# DIP2350_RC0.net
KiCad netlist of a schematic drawn in Altium Designer
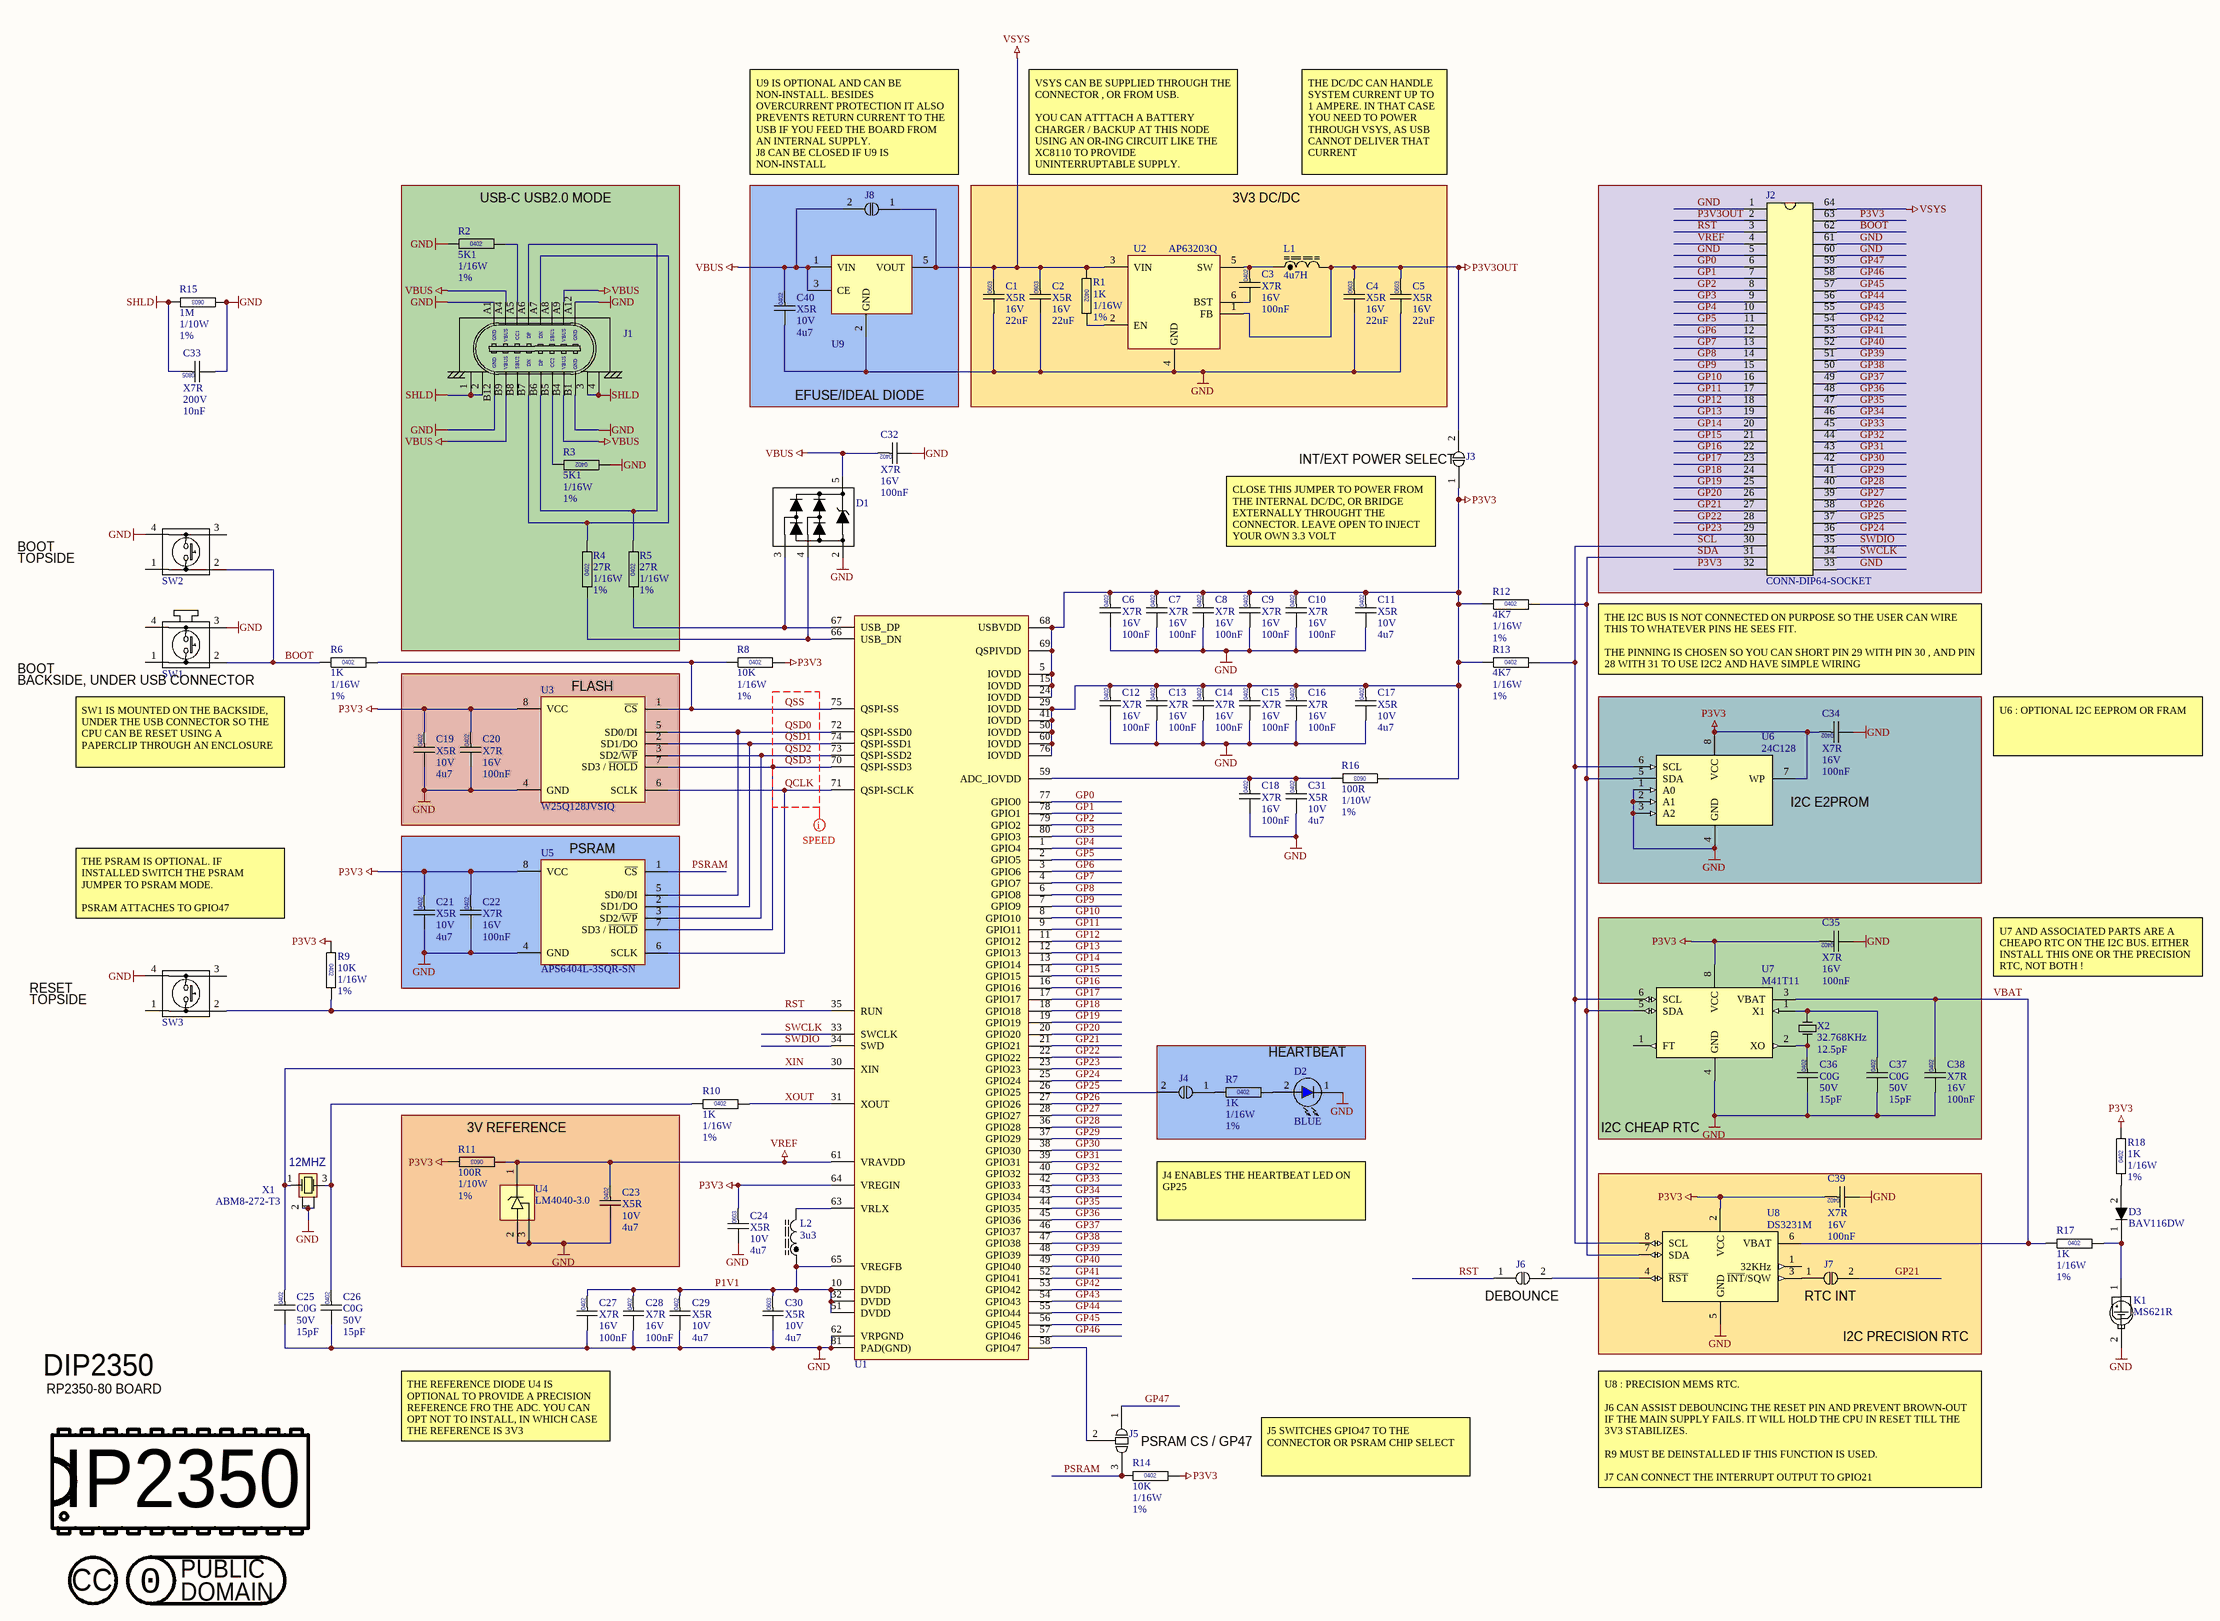
[diagram p0: DIP2350 RC0.SchDoc]

(export (version "E")
  (design (tool "Eeschema 10.0.6"))
  (components
    (comp (ref "C1")
      (value "CAP0603")
      (footprint "CAPC0603")
      (description "CAPACITOR,CERAMIC,22uF,16V,X5R,0603")
      (fields
        (field (name "DIELECTRIC") "X5R")
        (field (name "VOLTAGE") "16V")
        (field (name "CAPACITANCE") "22uF")
      )
      (libsource (lib "CAPACITORS") (part "CAPC-0603-22uF-16V-X5R"))
    )
    (comp (ref "C2")
      (value "CAP0603")
      (footprint "CAPC0603")
      (description "CAPACITOR,CERAMIC,22uF,16V,X5R,0603")
      (fields
        (field (name "DIELECTRIC") "X5R")
        (field (name "VOLTAGE") "16V")
        (field (name "CAPACITANCE") "22uF")
      )
      (libsource (lib "CAPACITORS") (part "CAPC-0603-22uF-16V-X5R"))
    )
    (comp (ref "C3")
      (value "CAP0402")
      (footprint "CAPC0402")
      (description "CAPACITOR,CERAMIC,100nF,16V,X7R,0402")
      (fields
        (field (name "DIELECTRIC") "X7R")
        (field (name "VOLTAGE") "16V")
        (field (name "CAPACITANCE") "100nF")
      )
      (libsource (lib "CAPACITORS") (part "CAPC-0402-100nF-16V-X7R"))
    )
    (comp (ref "C4")
      (value "CAP0603")
      (footprint "CAPC0603")
      (description "CAPACITOR,CERAMIC,22uF,16V,X5R,0603")
      (fields
        (field (name "DIELECTRIC") "X5R")
        (field (name "VOLTAGE") "16V")
        (field (name "CAPACITANCE") "22uF")
      )
      (libsource (lib "CAPACITORS") (part "CAPC-0603-22uF-16V-X5R"))
    )
    (comp (ref "C5")
      (value "CAP0603")
      (footprint "CAPC0603")
      (description "CAPACITOR,CERAMIC,22uF,16V,X5R,0603")
      (fields
        (field (name "DIELECTRIC") "X5R")
        (field (name "VOLTAGE") "16V")
        (field (name "CAPACITANCE") "22uF")
      )
      (libsource (lib "CAPACITORS") (part "CAPC-0603-22uF-16V-X5R"))
    )
    (comp (ref "C6")
      (value "CAP0402")
      (footprint "CAPC0402")
      (description "CAPACITOR,CERAMIC,100nF,16V,X7R,0402")
      (fields
        (field (name "DIELECTRIC") "X7R")
        (field (name "VOLTAGE") "16V")
        (field (name "CAPACITANCE") "100nF")
      )
      (libsource (lib "CAPACITORS") (part "CAPC-0402-100nF-16V-X7R"))
    )
    (comp (ref "C7")
      (value "CAP0402")
      (footprint "CAPC0402")
      (description "CAPACITOR,CERAMIC,100nF,16V,X7R,0402")
      (fields
        (field (name "DIELECTRIC") "X7R")
        (field (name "VOLTAGE") "16V")
        (field (name "CAPACITANCE") "100nF")
      )
      (libsource (lib "CAPACITORS") (part "CAPC-0402-100nF-16V-X7R"))
    )
    (comp (ref "C8")
      (value "CAP0402")
      (footprint "CAPC0402")
      (description "CAPACITOR,CERAMIC,100nF,16V,X7R,0402")
      (fields
        (field (name "DIELECTRIC") "X7R")
        (field (name "VOLTAGE") "16V")
        (field (name "CAPACITANCE") "100nF")
      )
      (libsource (lib "CAPACITORS") (part "CAPC-0402-100nF-16V-X7R"))
    )
    (comp (ref "C9")
      (value "CAP0402")
      (footprint "CAPC0402")
      (description "CAPACITOR,CERAMIC,100nF,16V,X7R,0402")
      (fields
        (field (name "DIELECTRIC") "X7R")
        (field (name "VOLTAGE") "16V")
        (field (name "CAPACITANCE") "100nF")
      )
      (libsource (lib "CAPACITORS") (part "CAPC-0402-100nF-16V-X7R"))
    )
    (comp (ref "C10")
      (value "CAP0402")
      (footprint "CAPC0402")
      (description "CAPACITOR,CERAMIC,100nF,16V,X7R,0402")
      (fields
        (field (name "DIELECTRIC") "X7R")
        (field (name "VOLTAGE") "16V")
        (field (name "CAPACITANCE") "100nF")
      )
      (libsource (lib "CAPACITORS") (part "CAPC-0402-100nF-16V-X7R"))
    )
    (comp (ref "C11")
      (value "CAP0402")
      (footprint "CAPC0402")
      (description "CAPACITOR,CERAMIC,4u7,10V,X5R,0402")
      (fields
        (field (name "DIELECTRIC") "X5R")
        (field (name "VOLTAGE") "10V")
        (field (name "CAPACITANCE") "4u7")
      )
      (libsource (lib "CAPACITORS") (part "CAPC-0402-4u7-10V-X5R"))
    )
    (comp (ref "C12")
      (value "CAP0402")
      (footprint "CAPC0402")
      (description "CAPACITOR,CERAMIC,100nF,16V,X7R,0402")
      (fields
        (field (name "DIELECTRIC") "X7R")
        (field (name "VOLTAGE") "16V")
        (field (name "CAPACITANCE") "100nF")
      )
      (libsource (lib "CAPACITORS") (part "CAPC-0402-100nF-16V-X7R"))
    )
    (comp (ref "C13")
      (value "CAP0402")
      (footprint "CAPC0402")
      (description "CAPACITOR,CERAMIC,100nF,16V,X7R,0402")
      (fields
        (field (name "DIELECTRIC") "X7R")
        (field (name "VOLTAGE") "16V")
        (field (name "CAPACITANCE") "100nF")
      )
      (libsource (lib "CAPACITORS") (part "CAPC-0402-100nF-16V-X7R"))
    )
    (comp (ref "C14")
      (value "CAP0402")
      (footprint "CAPC0402")
      (description "CAPACITOR,CERAMIC,100nF,16V,X7R,0402")
      (fields
        (field (name "DIELECTRIC") "X7R")
        (field (name "VOLTAGE") "16V")
        (field (name "CAPACITANCE") "100nF")
      )
      (libsource (lib "CAPACITORS") (part "CAPC-0402-100nF-16V-X7R"))
    )
    (comp (ref "C15")
      (value "CAP0402")
      (footprint "CAPC0402")
      (description "CAPACITOR,CERAMIC,100nF,16V,X7R,0402")
      (fields
        (field (name "DIELECTRIC") "X7R")
        (field (name "VOLTAGE") "16V")
        (field (name "CAPACITANCE") "100nF")
      )
      (libsource (lib "CAPACITORS") (part "CAPC-0402-100nF-16V-X7R"))
    )
    (comp (ref "C16")
      (value "CAP0402")
      (footprint "CAPC0402")
      (description "CAPACITOR,CERAMIC,100nF,16V,X7R,0402")
      (fields
        (field (name "DIELECTRIC") "X7R")
        (field (name "VOLTAGE") "16V")
        (field (name "CAPACITANCE") "100nF")
      )
      (libsource (lib "CAPACITORS") (part "CAPC-0402-100nF-16V-X7R"))
    )
    (comp (ref "C17")
      (value "CAP0402")
      (footprint "CAPC0402")
      (description "CAPACITOR,CERAMIC,4u7,10V,X5R,0402")
      (fields
        (field (name "DIELECTRIC") "X5R")
        (field (name "VOLTAGE") "10V")
        (field (name "CAPACITANCE") "4u7")
      )
      (libsource (lib "CAPACITORS") (part "CAPC-0402-4u7-10V-X5R"))
    )
    (comp (ref "C18")
      (value "CAP0402")
      (footprint "CAPC0402")
      (description "CAPACITOR,CERAMIC,100nF,16V,X7R,0402")
      (fields
        (field (name "DIELECTRIC") "X7R")
        (field (name "VOLTAGE") "16V")
        (field (name "CAPACITANCE") "100nF")
      )
      (libsource (lib "CAPACITORS") (part "CAPC-0402-100nF-16V-X7R"))
    )
    (comp (ref "C19")
      (value "CAP0402")
      (footprint "CAPC0402")
      (description "CAPACITOR,CERAMIC,4u7,10V,X5R,0402")
      (fields
        (field (name "DIELECTRIC") "X5R")
        (field (name "VOLTAGE") "10V")
        (field (name "CAPACITANCE") "4u7")
      )
      (libsource (lib "CAPACITORS") (part "CAPC-0402-4u7-10V-X5R"))
    )
    (comp (ref "C20")
      (value "CAP0402")
      (footprint "CAPC0402")
      (description "CAPACITOR,CERAMIC,100nF,16V,X7R,0402")
      (fields
        (field (name "DIELECTRIC") "X7R")
        (field (name "VOLTAGE") "16V")
        (field (name "CAPACITANCE") "100nF")
      )
      (libsource (lib "CAPACITORS") (part "CAPC-0402-100nF-16V-X7R"))
    )
    (comp (ref "C21")
      (value "CAP0402")
      (footprint "CAPC0402")
      (description "CAPACITOR,CERAMIC,4u7,10V,X5R,0402")
      (fields
        (field (name "DIELECTRIC") "X5R")
        (field (name "VOLTAGE") "10V")
        (field (name "CAPACITANCE") "4u7")
      )
      (libsource (lib "CAPACITORS") (part "CAPC-0402-4u7-10V-X5R"))
    )
    (comp (ref "C22")
      (value "CAP0402")
      (footprint "CAPC0402")
      (description "CAPACITOR,CERAMIC,100nF,16V,X7R,0402")
      (fields
        (field (name "DIELECTRIC") "X7R")
        (field (name "VOLTAGE") "16V")
        (field (name "CAPACITANCE") "100nF")
      )
      (libsource (lib "CAPACITORS") (part "CAPC-0402-100nF-16V-X7R"))
    )
    (comp (ref "C23")
      (value "CAP0402")
      (footprint "CAPC0402")
      (description "CAPACITOR,CERAMIC,4u7,10V,X5R,0402")
      (fields
        (field (name "DIELECTRIC") "X5R")
        (field (name "VOLTAGE") "10V")
        (field (name "CAPACITANCE") "4u7")
      )
      (libsource (lib "CAPACITORS") (part "CAPC-0402-4u7-10V-X5R"))
    )
    (comp (ref "C24")
      (value "CAP0603")
      (footprint "CAPC0603")
      (description "CAPACITOR,CERAMIC,4u7,10V,X5R,0603")
      (fields
        (field (name "DIELECTRIC") "X5R")
        (field (name "VOLTAGE") "10V")
        (field (name "CAPACITANCE") "4u7")
      )
      (libsource (lib "CAPACITORS") (part "CAPC-0603-4u7-10V-X5R"))
    )
    (comp (ref "C25")
      (value "CAP0603")
      (footprint "CAPC0402")
      (description "CAPACITOR,CERAMIC,15pF,50V,C0G,0402")
      (fields
        (field (name "DIELECTRIC") "C0G")
        (field (name "VOLTAGE") "50V")
        (field (name "CAPACITANCE") "15pF")
      )
      (libsource (lib "CAPACITORS") (part "CAPC-0402-15PF-50V-C0G"))
    )
    (comp (ref "C26")
      (value "CAP0603")
      (footprint "CAPC0402")
      (description "CAPACITOR,CERAMIC,15pF,50V,C0G,0402")
      (fields
        (field (name "DIELECTRIC") "C0G")
        (field (name "VOLTAGE") "50V")
        (field (name "CAPACITANCE") "15pF")
      )
      (libsource (lib "CAPACITORS") (part "CAPC-0402-15PF-50V-C0G"))
    )
    (comp (ref "C27")
      (value "CAP0402")
      (footprint "CAPC0402")
      (description "CAPACITOR,CERAMIC,100nF,16V,X7R,0402")
      (fields
        (field (name "DIELECTRIC") "X7R")
        (field (name "VOLTAGE") "16V")
        (field (name "CAPACITANCE") "100nF")
      )
      (libsource (lib "CAPACITORS") (part "CAPC-0402-100nF-16V-X7R"))
    )
    (comp (ref "C28")
      (value "CAP0402")
      (footprint "CAPC0402")
      (description "CAPACITOR,CERAMIC,100nF,16V,X7R,0402")
      (fields
        (field (name "DIELECTRIC") "X7R")
        (field (name "VOLTAGE") "16V")
        (field (name "CAPACITANCE") "100nF")
      )
      (libsource (lib "CAPACITORS") (part "CAPC-0402-100nF-16V-X7R"))
    )
    (comp (ref "C29")
      (value "CAP0402")
      (footprint "CAPC0402")
      (description "CAPACITOR,CERAMIC,4u7,10V,X5R,0402")
      (fields
        (field (name "DIELECTRIC") "X5R")
        (field (name "VOLTAGE") "10V")
        (field (name "CAPACITANCE") "4u7")
      )
      (libsource (lib "CAPACITORS") (part "CAPC-0402-4u7-10V-X5R"))
    )
    (comp (ref "C30")
      (value "CAP0603")
      (footprint "CAPC0603")
      (description "CAPACITOR,CERAMIC,4u7,10V,X5R,0603")
      (fields
        (field (name "DIELECTRIC") "X5R")
        (field (name "VOLTAGE") "10V")
        (field (name "CAPACITANCE") "4u7")
      )
      (libsource (lib "CAPACITORS") (part "CAPC-0603-4u7-10V-X5R"))
    )
    (comp (ref "C31")
      (value "CAP0402")
      (footprint "CAPC0402")
      (description "CAPACITOR,CERAMIC,4u7,10V,X5R,0402")
      (fields
        (field (name "DIELECTRIC") "X5R")
        (field (name "VOLTAGE") "10V")
        (field (name "CAPACITANCE") "4u7")
      )
      (libsource (lib "CAPACITORS") (part "CAPC-0402-4u7-10V-X5R"))
    )
    (comp (ref "C32")
      (value "CAP0402")
      (footprint "CAPC0402")
      (description "CAPACITOR,CERAMIC,100nF,16V,X7R,0402")
      (fields
        (field (name "DIELECTRIC") "X7R")
        (field (name "VOLTAGE") "16V")
        (field (name "CAPACITANCE") "100nF")
      )
      (libsource (lib "CAPACITORS") (part "CAPC-0402-100nF-16V-X7R"))
    )
    (comp (ref "C33")
      (value "CAP0805")
      (footprint "CAPC0805")
      (description "CAPACITOR,CERAMIC,10nF,200V,X7R,0805 (2012),ESD")
      (fields
        (field (name "DIELECTRIC") "X7R")
        (field (name "VOLTAGE") "200V")
        (field (name "CAPACITANCE") "10nF")
      )
      (libsource (lib "CAPACITORS") (part "CAPC-0805-10nF-200V-ESD"))
    )
    (comp (ref "C34")
      (value "CAP0402")
      (footprint "CAPC0402")
      (description "CAPACITOR,CERAMIC,100nF,16V,X7R,0402")
      (fields
        (field (name "DIELECTRIC") "X7R")
        (field (name "VOLTAGE") "16V")
        (field (name "CAPACITANCE") "100nF")
      )
      (libsource (lib "CAPACITORS") (part "CAPC-0402-100nF-16V-X7R"))
    )
    (comp (ref "C35")
      (value "CAP0402")
      (footprint "CAPC0402")
      (description "CAPACITOR,CERAMIC,100nF,16V,X7R,0402")
      (fields
        (field (name "DIELECTRIC") "X7R")
        (field (name "VOLTAGE") "16V")
        (field (name "CAPACITANCE") "100nF")
      )
      (libsource (lib "CAPACITORS") (part "CAPC-0402-100nF-16V-X7R"))
    )
    (comp (ref "C36")
      (value "CAP0603")
      (footprint "CAPC0402")
      (description "CAPACITOR,CERAMIC,15pF,50V,C0G,0402")
      (fields
        (field (name "DIELECTRIC") "C0G")
        (field (name "VOLTAGE") "50V")
        (field (name "CAPACITANCE") "15pF")
      )
      (libsource (lib "CAPACITORS") (part "CAPC-0402-15PF-50V-C0G"))
    )
    (comp (ref "C37")
      (value "CAP0603")
      (footprint "CAPC0402")
      (description "CAPACITOR,CERAMIC,15pF,50V,C0G,0402")
      (fields
        (field (name "DIELECTRIC") "C0G")
        (field (name "VOLTAGE") "50V")
        (field (name "CAPACITANCE") "15pF")
      )
      (libsource (lib "CAPACITORS") (part "CAPC-0402-15PF-50V-C0G"))
    )
    (comp (ref "C38")
      (value "CAP0402")
      (footprint "CAPC0402")
      (description "CAPACITOR,CERAMIC,100nF,16V,X7R,0402")
      (fields
        (field (name "DIELECTRIC") "X7R")
        (field (name "VOLTAGE") "16V")
        (field (name "CAPACITANCE") "100nF")
      )
      (libsource (lib "CAPACITORS") (part "CAPC-0402-100nF-16V-X7R"))
    )
    (comp (ref "C39")
      (value "CAP0402")
      (footprint "CAPC0402")
      (description "CAPACITOR,CERAMIC,100nF,16V,X7R,0402")
      (fields
        (field (name "DIELECTRIC") "X7R")
        (field (name "VOLTAGE") "16V")
        (field (name "CAPACITANCE") "100nF")
      )
      (libsource (lib "CAPACITORS") (part "CAPC-0402-100nF-16V-X7R"))
    )
    (comp (ref "C40")
      (value "CAP0402")
      (footprint "CAPC0402")
      (description "CAPACITOR,CERAMIC,4u7,10V,X5R,0402")
      (fields
        (field (name "DIELECTRIC") "X5R")
        (field (name "VOLTAGE") "10V")
        (field (name "CAPACITANCE") "4u7")
      )
      (libsource (lib "CAPACITORS") (part "CAPC-0402-4u7-10V-X5R"))
    )
    (comp (ref "D1")
      (value "TVS-WURTH-824011")
      (footprint "SOT23-5")
      (description "DIODE,TVS,DUAL,UNIDIRECTIONAL,USB")
      (libsource (lib "DIODES") (part "TVS-WURTH-824011"))
    )
    (comp (ref "D2")
      (value "BLUE")
      (footprint "LED-0603-BLUE")
      (description "LED,BLUE,0603")
      (libsource (lib "LED") (part "LED-WURTH-150060BS75000"))
    )
    (comp (ref "D3")
      (value "BAV116DW")
      (footprint "SOD323")
      (description "DIODE,75V,215mA,SOD323,LOW LEAKAGE")
      (libsource (lib "DIODES") (part "DIODE-DIODES-BAV116WS"))
    )
    (comp (ref "J1")
      (value "CONN-USBC-USB2-HOR")
      (footprint "CONN-GCT-USB4085")
      (description "CONN,USB-C,16P,RA,TH,8.94X9.17")
      (libsource (lib "CONNECTORS") (part "CONN-USBC-USB2-HOR"))
    )
    (comp (ref "J2")
      (value "CONN-DIP64-SOCKET")
      (footprint "CONN-DIP64-SOCKET")
      (libsource (lib "CONNECTORS") (part "CONN-DIP64-SOCKET"))
    )
    (comp (ref "J3")
      (value "SOLDERPAD-2")
      (footprint "SOLDERPAD-2")
      (libsource (lib "BOARDFEATURES") (part "SOLDERPAD-2"))
    )
    (comp (ref "J4")
      (value "SOLDERPAD-2")
      (footprint "SOLDERPAD-2")
      (libsource (lib "BOARDFEATURES") (part "SOLDERPAD-2"))
    )
    (comp (ref "J5")
      (value "SOLDERPAD-3")
      (footprint "SOLDERPAD-3")
      (libsource (lib "BOARDFEATURES") (part "SOLDERPAD-3"))
    )
    (comp (ref "J6")
      (value "SOLDERPAD-2")
      (footprint "SOLDERPAD-2")
      (libsource (lib "BOARDFEATURES") (part "SOLDERPAD-2"))
    )
    (comp (ref "J7")
      (value "SOLDERPAD-2")
      (footprint "SOLDERPAD-2")
      (libsource (lib "BOARDFEATURES") (part "SOLDERPAD-2"))
    )
    (comp (ref "J8")
      (value "SOLDERPAD-2")
      (footprint "SOLDERPAD-2")
      (libsource (lib "BOARDFEATURES") (part "SOLDERPAD-2"))
    )
    (comp (ref "K1")
      (value "MS621R")
      (footprint "BAT-SEIKO-MS621R")
      (description "BAT,3V,SMD,SEIKO MS621R")
      (libsource (lib "BATTERIES") (part "BAT-SEIKO-MS621R"))
    )
    (comp (ref "L1")
      (value "4u7H")
      (footprint "IND-ABRACON-ASPI-3012S-3R9N-T")
      (description "IND,4.7uH,1.06A,3X3, NRH3012T4R7MN")
      (fields (field (name "Comment") "4.7uH"))
      (libsource (lib "INDUCTORS") (part "IND-TAIYO-NRH3012T4R7MN"))
    )
    (comp (ref "L2")
      (value "3u3")
      (footprint "IND-ABRACON-B201610S3R3-101-T")
      (description "IND,3U3,RP2350, ABRACON AOTA-B201610S3R3-101-T")
      (fields (field (name "Comment") "AOTA-B201610S3R3-101-T"))
      (libsource (lib "INDUCTORS") (part "IND-ABRACON-AOTA-B201610S3R3-101-T"))
    )
    (comp (ref "LOGO1")
      (value "LOGO-LICENSE-CC0-PUBLIC")
      (footprint "LOGO-LICENSE-CC0-PUBLIC")
      (libsource (lib "LOGO") (part "LOGO-LICENSE-CC0-PUBLIC"))
    )
    (comp (ref "LOGO2")
      (value "LOGO-LICENSE-CC")
      (footprint "LOGO-LICENSE-CC")
      (libsource (lib "LOGO") (part "LOGO-LICENSE-CC"))
    )
    (comp (ref "R1")
      (value "1K")
      (footprint "RESC0402")
      (description "RESISTOR,1K,1%,63mW,0402 (1005)")
      (fields
        (field (name "POWER") "1/16W")
        (field (name "TOLERANCE") "1%")
        (field (name "Comment") "RESC0402")
      )
      (libsource (lib "RESISTORS") (part "RESC-0402-1K-1%-1/10W"))
    )
    (comp (ref "R2")
      (value "5K1")
      (footprint "RESC0402")
      (description "RESISTOR,5K1,1%,63mW,0402 (1005)")
      (fields
        (field (name "POWER") "1/16W")
        (field (name "TOLERANCE") "1%")
        (field (name "Comment") "RESC0402")
      )
      (libsource (lib "RESISTORS") (part "RESC-0402-5K1-1%-1/10W"))
    )
    (comp (ref "R3")
      (value "5K1")
      (footprint "RESC0402")
      (description "RESISTOR,5K1,1%,63mW,0402 (1005)")
      (fields
        (field (name "POWER") "1/16W")
        (field (name "TOLERANCE") "1%")
        (field (name "Comment") "RESC0402")
      )
      (libsource (lib "RESISTORS") (part "RESC-0402-5K1-1%-1/10W"))
    )
    (comp (ref "R4")
      (value "27R")
      (footprint "RESC0402")
      (description "RESISTOR,27R,1%,63mW,0402 (1005)")
      (fields
        (field (name "POWER") "1/16W")
        (field (name "TOLERANCE") "1%")
        (field (name "Comment") "RESC0402")
      )
      (libsource (lib "RESISTORS") (part "RESC-0402-27R-1%-1/10W"))
    )
    (comp (ref "R5")
      (value "27R")
      (footprint "RESC0402")
      (description "RESISTOR,27R,1%,63mW,0402 (1005)")
      (fields
        (field (name "POWER") "1/16W")
        (field (name "TOLERANCE") "1%")
        (field (name "Comment") "RESC0402")
      )
      (libsource (lib "RESISTORS") (part "RESC-0402-27R-1%-1/10W"))
    )
    (comp (ref "R6")
      (value "1K")
      (footprint "RESC0402")
      (description "RESISTOR,1K,1%,63mW,0402 (1005)")
      (fields
        (field (name "POWER") "1/16W")
        (field (name "TOLERANCE") "1%")
        (field (name "Comment") "RESC0402")
      )
      (libsource (lib "RESISTORS") (part "RESC-0402-1K-1%-1/10W"))
    )
    (comp (ref "R7")
      (value "1K")
      (footprint "RESC0402")
      (description "RESISTOR,1K,1%,63mW,0402 (1005)")
      (fields
        (field (name "POWER") "1/16W")
        (field (name "TOLERANCE") "1%")
        (field (name "Comment") "RESC0402")
      )
      (libsource (lib "RESISTORS") (part "RESC-0402-1K-1%-1/10W"))
    )
    (comp (ref "R8")
      (value "10K")
      (footprint "RESC0402")
      (description "RESISTOR,10K,1%,63mW,0402 (1005)")
      (fields
        (field (name "POWER") "1/16W")
        (field (name "TOLERANCE") "1%")
        (field (name "Comment") "RESC0402")
      )
      (libsource (lib "RESISTORS") (part "RESC-0402-10K-1%-1/10W"))
    )
    (comp (ref "R9")
      (value "10K")
      (footprint "RESC0402")
      (description "RESISTOR,10K,1%,63mW,0402 (1005)")
      (fields
        (field (name "POWER") "1/16W")
        (field (name "TOLERANCE") "1%")
        (field (name "Comment") "RESC0402")
      )
      (libsource (lib "RESISTORS") (part "RESC-0402-10K-1%-1/10W"))
    )
    (comp (ref "R10")
      (value "1K")
      (footprint "RESC0402")
      (description "RESISTOR,1K,1%,63mW,0402 (1005)")
      (fields
        (field (name "POWER") "1/16W")
        (field (name "TOLERANCE") "1%")
        (field (name "Comment") "RESC0402")
      )
      (libsource (lib "RESISTORS") (part "RESC-0402-1K-1%-1/10W"))
    )
    (comp (ref "R11")
      (value "100R")
      (footprint "RESC0603")
      (description "RESISTOR,100R,1%,100mW,0603 (1608)")
      (fields
        (field (name "POWER") "1/10W")
        (field (name "TOLERANCE") "1%")
        (field (name "Comment") "RESC0603")
      )
      (libsource (lib "RESISTORS") (part "RESC-0603-100R-1%-1/10W"))
    )
    (comp (ref "R12")
      (value "4K7")
      (footprint "RESC0402")
      (description "RESISTOR,4K7,1%,63mW,0402 (1005)")
      (fields
        (field (name "POWER") "1/16W")
        (field (name "TOLERANCE") "1%")
        (field (name "Comment") "RESC0402")
      )
      (libsource (lib "RESISTORS") (part "RESC-0402-4K7-1%-1/10W"))
    )
    (comp (ref "R13")
      (value "4K7")
      (footprint "RESC0402")
      (description "RESISTOR,4K7,1%,63mW,0402 (1005)")
      (fields
        (field (name "POWER") "1/16W")
        (field (name "TOLERANCE") "1%")
        (field (name "Comment") "RESC0402")
      )
      (libsource (lib "RESISTORS") (part "RESC-0402-4K7-1%-1/10W"))
    )
    (comp (ref "R14")
      (value "10K")
      (footprint "RESC0402")
      (description "RESISTOR,10K,1%,63mW,0402 (1005)")
      (fields
        (field (name "POWER") "1/16W")
        (field (name "TOLERANCE") "1%")
        (field (name "Comment") "RESC0402")
      )
      (libsource (lib "RESISTORS") (part "RESC-0402-10K-1%-1/10W"))
    )
    (comp (ref "R15")
      (value "1M")
      (footprint "RESC0603")
      (description "RESISTOR,1M,1%,100mW,0603 (1608)")
      (fields
        (field (name "POWER") "1/10W")
        (field (name "TOLERANCE") "1%")
        (field (name "Comment") "RESC0603")
      )
      (libsource (lib "RESISTORS") (part "RESC-0603-1M-1%-1/10W"))
    )
    (comp (ref "R16")
      (value "100R")
      (footprint "RESC0603")
      (description "RESISTOR,100R,1%,100mW,0603 (1608)")
      (fields
        (field (name "POWER") "1/10W")
        (field (name "TOLERANCE") "1%")
        (field (name "Comment") "RESC0603")
      )
      (libsource (lib "RESISTORS") (part "RESC-0603-100R-1%-1/10W"))
    )
    (comp (ref "R17")
      (value "1K")
      (footprint "RESC0402")
      (description "RESISTOR,1K,1%,63mW,0402 (1005)")
      (fields
        (field (name "POWER") "1/16W")
        (field (name "TOLERANCE") "1%")
        (field (name "Comment") "RESC0402")
      )
      (libsource (lib "RESISTORS") (part "RESC-0402-1K-1%-1/10W"))
    )
    (comp (ref "R18")
      (value "1K")
      (footprint "RESC0402")
      (description "RESISTOR,1K,1%,63mW,0402 (1005)")
      (fields
        (field (name "POWER") "1/16W")
        (field (name "TOLERANCE") "1%")
        (field (name "Comment") "RESC0402")
      )
      (libsource (lib "RESISTORS") (part "RESC-0402-1K-1%-1/10W"))
    )
    (comp (ref "SW1")
      (value "SWITCH-E-SWITCH-TL1016")
      (footprint "SWITCH-ESWITCH-TL1016")
      (description "SW,SMD,TACT,4PIN,2.9X3.5,4PIN,SIDE ACTUATOR")
      (libsource (lib "SWITCH") (part "SWITCH-E-SWITCH-TL1016"))
    )
    (comp (ref "SW2")
      (value "SWITCH-PANASONIC-EVP-AA202K")
      (footprint "SWITCH-PANASONIC-EVP-AA202K")
      (description "SW,SMD,TACT,4PIN,2.9X3.5,4PIN")
      (libsource (lib "SWITCH") (part "SWITCH-PANASONIC-EVP-AA202K"))
    )
    (comp (ref "SW3")
      (value "SWITCH-PANASONIC-EVP-AA202K")
      (footprint "SWITCH-PANASONIC-EVP-AA202K")
      (description "SW,SMD,TACT,4PIN,2.9X3.5,4PIN")
      (libsource (lib "SWITCH") (part "SWITCH-PANASONIC-EVP-AA202K"))
    )
    (comp (ref "U1")
      (value "IC-RP2350-DIP64")
      (footprint "QFN40P1000X1000X90_HS-81N")
      (description "IC,CPU,RP2350B,QFN80")
      (libsource (lib "IC-CPU") (part "IC-RP2350-DIP64"))
    )
    (comp (ref "U2")
      (value "AP63203Q")
      (footprint "SOT23-6")
      (description "IC,PMIC,STEP-DOWN, 2A 3.3V")
      (libsource (lib "IC-REG") (part "IC-DIODES-AP63203Q"))
    )
    (comp (ref "U3")
      (value "W25Q128JVSIQ")
      (footprint "SO127P600-8N")
      (description "IC,FLASH,QSPI,16Mx8")
      (libsource (lib "IC-SPI") (part "IC-WINBOND-W25Q128JVSIQ"))
    )
    (comp (ref "U4")
      (value "LM4040-3.0")
      (footprint "SOT23")
      (description "IC,VOLTAGE REFERENCE,3.0V")
      (libsource (lib "IC-REG") (part "IC-TI-LM4040-3"))
    )
    (comp (ref "U5")
      (value "APS6404L-3SQR-SN")
      (footprint "SO127P600-8N")
      (description "IC,PSRAM,QSPI,8Mx8,SO8")
      (libsource (lib "IC-SPI") (part "IC-APMEMORY-APS6404L-3SQR-SN"))
    )
    (comp (ref "U6")
      (value "24C128")
      (footprint "SO127P600-8N")
      (description "IC,EEPROM,I2C, 128KBIT")
      (libsource (lib "IC-I2C") (part "IC-GENERIC-24C128"))
    )
    (comp (ref "U7")
      (value "M41T11")
      (footprint "SO127P600-8N")
      (description "IC,RTC+RAM+VBAT,I2C 1101000,  SMHDDMY")
      (libsource (lib "IC-I2C") (part "IC-ST-M41T11"))
    )
    (comp (ref "U8")
      (value "DS3231M")
      (footprint "SO127P600-8N")
      (description "IC,RTC,I2C,DS3231M")
      (libsource (lib "IC-I2C") (part "IC-ANALOG-DS3231M"))
    )
    (comp (ref "U9")
      (value "XC8110")
      (footprint "SOT23-5")
      (description "IC,PMIC,IDEAL DIODE ORING CONTROLLER")
      (libsource (lib "IC-REG") (part "IC-TOREX-XC8110"))
    )
    (comp (ref "X1")
      (value "ABM8-272-T3")
      (footprint "XTAL-ABRACON-ABM8-272-T3")
      (description "XTAL,12MHZ,RP2350")
      (libsource (lib "CRYSTALS") (part "XTAL-ABRACON-ABM8-272-T3"))
    )
    (comp (ref "X2")
      (value "32.768KHz")
      (footprint "XTAL-3215")
      (description "XTAL,32.768KHz,12.5PF,3215")
      (fields (field (name "LOAD") "12.5pF") (field (name "Comment") "CRYSTAL-2PIN"))
      (libsource (lib "XTAL") (part "XTAL-RALTRON-RT3215-32.768-12.5-TR-10PPM"))
    )
  )
  (nets
    (net (code "1") (name "/BOOT") (class "Default")
      (node (ref "J2") (pin "62") (pinfunction "38_62") (pintype "passive"))
      (node (ref "R6") (pin "1") (pintype "passive"))
      (node (ref "SW1") (pin "2") (pinfunction "2_2") (pintype "passive"))
      (node (ref "SW2") (pin "2") (pinfunction "2_2") (pintype "passive"))
    )
    (net (code "2") (name "/GP0") (class "Default")
      (node (ref "J2") (pin "6") (pinfunction "6_6") (pintype "passive"))
      (node (ref "U1") (pin "77") (pinfunction "GPIO0_77") (pintype "passive"))
    )
    (net (code "3") (name "/GP1") (class "Default")
      (node (ref "J2") (pin "7") (pinfunction "7_7") (pintype "passive"))
      (node (ref "U1") (pin "78") (pinfunction "GPIO1_78") (pintype "passive"))
    )
    (net (code "4") (name "/GP2") (class "Default")
      (node (ref "J2") (pin "8") (pinfunction "8_8") (pintype "passive"))
      (node (ref "U1") (pin "79") (pinfunction "GPIO2_79") (pintype "passive"))
    )
    (net (code "5") (name "/GP3") (class "Default")
      (node (ref "J2") (pin "9") (pinfunction "9_9") (pintype "passive"))
      (node (ref "U1") (pin "80") (pinfunction "GPIO3_80") (pintype "passive"))
    )
    (net (code "6") (name "/GP4") (class "Default")
      (node (ref "J2") (pin "10") (pinfunction "10_10") (pintype "passive"))
      (node (ref "U1") (pin "1") (pinfunction "GPIO4_1") (pintype "passive"))
    )
    (net (code "7") (name "/GP5") (class "Default")
      (node (ref "J2") (pin "11") (pinfunction "11_11") (pintype "passive"))
      (node (ref "U1") (pin "2") (pinfunction "GPIO5_2") (pintype "passive"))
    )
    (net (code "8") (name "/GP6") (class "Default")
      (node (ref "J2") (pin "12") (pinfunction "12_12") (pintype "passive"))
      (node (ref "U1") (pin "3") (pinfunction "GPIO6_3") (pintype "passive"))
    )
    (net (code "9") (name "/GP7") (class "Default")
      (node (ref "J2") (pin "13") (pinfunction "13_13") (pintype "passive"))
      (node (ref "U1") (pin "4") (pinfunction "GPIO7_4") (pintype "passive"))
    )
    (net (code "10") (name "/GP8") (class "Default")
      (node (ref "J2") (pin "14") (pinfunction "14_14") (pintype "passive"))
      (node (ref "U1") (pin "6") (pinfunction "GPIO8_6") (pintype "passive"))
    )
    (net (code "11") (name "/GP9") (class "Default")
      (node (ref "J2") (pin "15") (pinfunction "15_15") (pintype "passive"))
      (node (ref "U1") (pin "7") (pinfunction "GPIO9_7") (pintype "passive"))
    )
    (net (code "12") (name "/GP10") (class "Default")
      (node (ref "J2") (pin "16") (pinfunction "16_16") (pintype "passive"))
      (node (ref "U1") (pin "8") (pinfunction "GPIO10_8") (pintype "passive"))
    )
    (net (code "13") (name "/GP11") (class "Default")
      (node (ref "J2") (pin "17") (pinfunction "17_17") (pintype "passive"))
      (node (ref "U1") (pin "9") (pinfunction "GPIO11_9") (pintype "passive"))
    )
    (net (code "14") (name "/GP12") (class "Default")
      (node (ref "J2") (pin "18") (pinfunction "18_18") (pintype "passive"))
      (node (ref "U1") (pin "11") (pinfunction "GPIO12_11") (pintype "passive"))
    )
    (net (code "15") (name "/GP13") (class "Default")
      (node (ref "J2") (pin "19") (pinfunction "19_19") (pintype "passive"))
      (node (ref "U1") (pin "12") (pinfunction "GPIO13_12") (pintype "passive"))
    )
    (net (code "16") (name "/GP14") (class "Default")
      (node (ref "J2") (pin "20") (pinfunction "20_20") (pintype "passive"))
      (node (ref "U1") (pin "13") (pinfunction "GPIO14_13") (pintype "passive"))
    )
    (net (code "17") (name "/GP15") (class "Default")
      (node (ref "J2") (pin "21") (pinfunction "21_21") (pintype "passive"))
      (node (ref "U1") (pin "14") (pinfunction "GPIO15_14") (pintype "passive"))
    )
    (net (code "18") (name "/GP16") (class "Default")
      (node (ref "J2") (pin "22") (pinfunction "22_22") (pintype "passive"))
      (node (ref "U1") (pin "16") (pinfunction "GPIO16_16") (pintype "passive"))
    )
    (net (code "19") (name "/GP17") (class "Default")
      (node (ref "J2") (pin "23") (pinfunction "23_23") (pintype "passive"))
      (node (ref "U1") (pin "17") (pinfunction "GPIO17_17") (pintype "passive"))
    )
    (net (code "20") (name "/GP18") (class "Default")
      (node (ref "J2") (pin "24") (pinfunction "24_24") (pintype "passive"))
      (node (ref "U1") (pin "18") (pinfunction "GPIO18_18") (pintype "passive"))
    )
    (net (code "21") (name "/GP19") (class "Default")
      (node (ref "J2") (pin "25") (pinfunction "25_25") (pintype "passive"))
      (node (ref "U1") (pin "19") (pinfunction "GPIO19_19") (pintype "passive"))
    )
    (net (code "22") (name "/GP20") (class "Default")
      (node (ref "J2") (pin "26") (pinfunction "26_26") (pintype "passive"))
      (node (ref "U1") (pin "20") (pinfunction "GPIO20_20") (pintype "passive"))
    )
    (net (code "23") (name "/GP21") (class "Default")
      (node (ref "J2") (pin "27") (pinfunction "27_27") (pintype "passive"))
      (node (ref "J7") (pin "2") (pinfunction "2_2") (pintype "passive"))
      (node (ref "U1") (pin "21") (pinfunction "GPIO21_21") (pintype "passive"))
    )
    (net (code "24") (name "/GP22") (class "Default")
      (node (ref "J2") (pin "28") (pinfunction "28_28") (pintype "passive"))
      (node (ref "U1") (pin "22") (pinfunction "GPIO22_22") (pintype "passive"))
    )
    (net (code "25") (name "/GP23") (class "Default")
      (node (ref "J2") (pin "29") (pinfunction "29_29") (pintype "passive"))
      (node (ref "U1") (pin "23") (pinfunction "GPIO23_23") (pintype "passive"))
    )
    (net (code "26") (name "/GP24") (class "Default")
      (node (ref "J2") (pin "36") (pinfunction "36_36") (pintype "passive"))
      (node (ref "U1") (pin "25") (pinfunction "GPIO24_25") (pintype "passive"))
    )
    (net (code "27") (name "/GP25") (class "Default")
      (node (ref "J2") (pin "37") (pinfunction "37_37") (pintype "passive"))
      (node (ref "J4") (pin "2") (pinfunction "2_2") (pintype "passive"))
      (node (ref "U1") (pin "26") (pinfunction "GPIO25_26") (pintype "passive"))
    )
    (net (code "28") (name "/GP26") (class "Default")
      (node (ref "J2") (pin "38") (pinfunction "38_38") (pintype "passive"))
      (node (ref "U1") (pin "27") (pinfunction "GPIO26_27") (pintype "passive"))
    )
    (net (code "29") (name "/GP27") (class "Default")
      (node (ref "J2") (pin "39") (pinfunction "39_39") (pintype "passive"))
      (node (ref "U1") (pin "28") (pinfunction "GPIO27_28") (pintype "passive"))
    )
    (net (code "30") (name "/GP28") (class "Default")
      (node (ref "J2") (pin "40") (pinfunction "40_40") (pintype "passive"))
      (node (ref "U1") (pin "36") (pinfunction "GPIO28_36") (pintype "passive"))
    )
    (net (code "31") (name "/GP29") (class "Default")
      (node (ref "J2") (pin "41") (pinfunction "33_41") (pintype "passive"))
      (node (ref "U1") (pin "37") (pinfunction "GPIO29_37") (pintype "passive"))
    )
    (net (code "32") (name "/GP30") (class "Default")
      (node (ref "J2") (pin "42") (pinfunction "34_42") (pintype "passive"))
      (node (ref "U1") (pin "38") (pinfunction "GPIO30_38") (pintype "passive"))
    )
    (net (code "33") (name "/GP31") (class "Default")
      (node (ref "J2") (pin "43") (pinfunction "35_43") (pintype "passive"))
      (node (ref "U1") (pin "39") (pinfunction "GPIO31_39") (pintype "passive"))
    )
    (net (code "34") (name "/GP32") (class "Default")
      (node (ref "J2") (pin "44") (pinfunction "36_44") (pintype "passive"))
      (node (ref "U1") (pin "40") (pinfunction "GPIO32_40") (pintype "passive"))
    )
    (net (code "35") (name "/GP33") (class "Default")
      (node (ref "J2") (pin "45") (pinfunction "37_45") (pintype "passive"))
      (node (ref "U1") (pin "42") (pinfunction "GPIO33_42") (pintype "passive"))
    )
    (net (code "36") (name "/GP34") (class "Default")
      (node (ref "J2") (pin "46") (pinfunction "38_46") (pintype "passive"))
      (node (ref "U1") (pin "43") (pinfunction "GPIO34_43") (pintype "passive"))
    )
    (net (code "37") (name "/GP35") (class "Default")
      (node (ref "J2") (pin "47") (pinfunction "39_47") (pintype "passive"))
      (node (ref "U1") (pin "44") (pinfunction "GPIO35_44") (pintype "passive"))
    )
    (net (code "38") (name "/GP36") (class "Default")
      (node (ref "J2") (pin "48") (pinfunction "40_48") (pintype "passive"))
      (node (ref "U1") (pin "45") (pinfunction "GPIO36_45") (pintype "passive"))
    )
    (net (code "39") (name "/GP37") (class "Default")
      (node (ref "J2") (pin "49") (pinfunction "33_49") (pintype "passive"))
      (node (ref "U1") (pin "46") (pinfunction "GPIO37_46") (pintype "passive"))
    )
    (net (code "40") (name "/GP38") (class "Default")
      (node (ref "J2") (pin "50") (pinfunction "34_50") (pintype "passive"))
      (node (ref "U1") (pin "47") (pinfunction "GPIO38_47") (pintype "passive"))
    )
    (net (code "41") (name "/GP39") (class "Default")
      (node (ref "J2") (pin "51") (pinfunction "35_51") (pintype "passive"))
      (node (ref "U1") (pin "48") (pinfunction "GPIO39_48") (pintype "passive"))
    )
    (net (code "42") (name "/GP40") (class "Default")
      (node (ref "J2") (pin "52") (pinfunction "36_52") (pintype "passive"))
      (node (ref "U1") (pin "49") (pinfunction "GPIO40_49") (pintype "passive"))
    )
    (net (code "43") (name "/GP41") (class "Default")
      (node (ref "J2") (pin "53") (pinfunction "37_53") (pintype "passive"))
      (node (ref "U1") (pin "52") (pinfunction "GPIO41_52") (pintype "passive"))
    )
    (net (code "44") (name "/GP42") (class "Default")
      (node (ref "J2") (pin "54") (pinfunction "38_54") (pintype "passive"))
      (node (ref "U1") (pin "53") (pinfunction "GPIO42_53") (pintype "passive"))
    )
    (net (code "45") (name "/GP43") (class "Default")
      (node (ref "J2") (pin "55") (pinfunction "39_55") (pintype "passive"))
      (node (ref "U1") (pin "54") (pinfunction "GPIO43_54") (pintype "passive"))
    )
    (net (code "46") (name "/GP44") (class "Default")
      (node (ref "J2") (pin "56") (pinfunction "40_56") (pintype "passive"))
      (node (ref "U1") (pin "55") (pinfunction "GPIO44_55") (pintype "passive"))
    )
    (net (code "47") (name "/GP45") (class "Default")
      (node (ref "J2") (pin "57") (pinfunction "33_57") (pintype "passive"))
      (node (ref "U1") (pin "56") (pinfunction "GPIO45_56") (pintype "passive"))
    )
    (net (code "48") (name "/GP46") (class "Default")
      (node (ref "J2") (pin "58") (pinfunction "34_58") (pintype "passive"))
      (node (ref "U1") (pin "57") (pinfunction "GPIO46_57") (pintype "passive"))
    )
    (net (code "49") (name "/GP47") (class "Default")
      (node (ref "J2") (pin "59") (pinfunction "35_59") (pintype "passive"))
      (node (ref "J5") (pin "1") (pinfunction "1_1") (pintype "passive"))
    )
    (net (code "50") (name "/P1V1") (class "Default")
      (node (ref "C27") (pin "1") (pintype "passive"))
      (node (ref "C28") (pin "1") (pintype "passive"))
      (node (ref "C29") (pin "1") (pintype "passive"))
      (node (ref "C30") (pin "1") (pintype "passive"))
      (node (ref "L2") (pin "1") (pinfunction "1_1") (pintype "passive"))
      (node (ref "U1") (pin "10") (pinfunction "DVDD_10") (pintype "passive"))
      (node (ref "U1") (pin "32") (pinfunction "DVDD_32") (pintype "passive"))
      (node (ref "U1") (pin "51") (pinfunction "DVDD_51") (pintype "passive"))
      (node (ref "U1") (pin "65") (pinfunction "VREGFB_65") (pintype "passive"))
    )
    (net (code "51") (name "/PSRAM") (class "Default")
      (node (ref "J5") (pin "3") (pinfunction "3_3") (pintype "passive"))
      (node (ref "R14") (pin "1") (pintype "passive"))
      (node (ref "U5") (pin "1") (pinfunction "~{CS}_1") (pintype "passive"))
    )
    (net (code "52") (name "/QCLK") (class "Default")
      (node (ref "U1") (pin "71") (pinfunction "QSPI-SCLK_71") (pintype "passive"))
      (node (ref "U3") (pin "6") (pinfunction "SCLK_6") (pintype "passive"))
      (node (ref "U5") (pin "6") (pinfunction "SCLK_6") (pintype "passive"))
    )
    (net (code "53") (name "/QSD0") (class "Default")
      (node (ref "U1") (pin "72") (pinfunction "QSPI-SSD0_72") (pintype "passive"))
      (node (ref "U3") (pin "5") (pinfunction "SD0/DI_5") (pintype "passive"))
      (node (ref "U5") (pin "5") (pinfunction "SD0/DI_5") (pintype "passive"))
    )
    (net (code "54") (name "/QSD1") (class "Default")
      (node (ref "U1") (pin "74") (pinfunction "QSPI-SSD1_74") (pintype "passive"))
      (node (ref "U3") (pin "2") (pinfunction "SD1/DO_2") (pintype "passive"))
      (node (ref "U5") (pin "2") (pinfunction "SD1/DO_2") (pintype "passive"))
    )
    (net (code "55") (name "/QSD2") (class "Default")
      (node (ref "U1") (pin "73") (pinfunction "QSPI-SSD2_73") (pintype "passive"))
      (node (ref "U3") (pin "3") (pinfunction "SD2/~{WP}_3") (pintype "passive"))
      (node (ref "U5") (pin "3") (pinfunction "SD2/~{WP}_3") (pintype "passive"))
    )
    (net (code "56") (name "/QSD3") (class "Default")
      (node (ref "U1") (pin "70") (pinfunction "QSPI-SSD3_70") (pintype "passive"))
      (node (ref "U3") (pin "7") (pinfunction "SD3_/_~{HOLD}_7") (pintype "passive"))
      (node (ref "U5") (pin "7") (pinfunction "SD3_/_~{HOLD}_7") (pintype "passive"))
    )
    (net (code "57") (name "/QSS") (class "Default")
      (node (ref "R6") (pin "2") (pintype "passive"))
      (node (ref "R8") (pin "1") (pintype "passive"))
      (node (ref "U1") (pin "75") (pinfunction "QSPI-SS_75") (pintype "passive"))
      (node (ref "U3") (pin "1") (pinfunction "~{CS}_1") (pintype "passive"))
    )
    (net (code "58") (name "/RST") (class "Default")
      (node (ref "J2") (pin "3") (pinfunction "3_3") (pintype "passive"))
      (node (ref "J6") (pin "1") (pinfunction "1_1") (pintype "passive"))
      (node (ref "R9") (pin "1") (pintype "passive"))
      (node (ref "SW3") (pin "2") (pinfunction "2_2") (pintype "passive"))
      (node (ref "U1") (pin "35") (pinfunction "RUN_35") (pintype "passive"))
    )
    (net (code "59") (name "/SCL") (class "Default")
      (node (ref "J2") (pin "30") (pinfunction "30_30") (pintype "passive"))
      (node (ref "R13") (pin "2") (pintype "passive"))
      (node (ref "U6") (pin "6") (pinfunction "SCL_6") (pintype "input"))
      (node (ref "U7") (pin "6") (pinfunction "SCL_6") (pintype "bidirectional"))
      (node (ref "U8") (pin "8") (pinfunction "SCL_8") (pintype "bidirectional"))
    )
    (net (code "60") (name "/SDA") (class "Default")
      (node (ref "J2") (pin "31") (pinfunction "31_31") (pintype "passive"))
      (node (ref "R12") (pin "2") (pintype "passive"))
      (node (ref "U6") (pin "5") (pinfunction "SDA_5") (pintype "open_collector"))
      (node (ref "U7") (pin "5") (pinfunction "SDA_5") (pintype "bidirectional"))
      (node (ref "U8") (pin "7") (pinfunction "SDA_7") (pintype "bidirectional"))
    )
    (net (code "61") (name "/SWCLK") (class "Default")
      (node (ref "J2") (pin "34") (pinfunction "34_34") (pintype "passive"))
      (node (ref "U1") (pin "33") (pinfunction "SWCLK_33") (pintype "passive"))
    )
    (net (code "62") (name "/SWDIO") (class "Default")
      (node (ref "J2") (pin "35") (pinfunction "35_35") (pintype "passive"))
      (node (ref "U1") (pin "34") (pinfunction "SWD_34") (pintype "passive"))
    )
    (net (code "63") (name "/VBAT") (class "Default")
      (node (ref "C38") (pin "1") (pintype "passive"))
      (node (ref "R17") (pin "1") (pintype "passive"))
      (node (ref "U7") (pin "3") (pinfunction "VBAT_3") (pintype "passive"))
      (node (ref "U8") (pin "6") (pinfunction "VBAT_6") (pintype "passive"))
    )
    (net (code "64") (name "/XIN") (class "Default")
      (node (ref "C25") (pin "1") (pintype "passive"))
      (node (ref "U1") (pin "30") (pinfunction "XIN_30") (pintype "passive"))
      (node (ref "X1") (pin "1") (pinfunction "1_1") (pintype "passive"))
    )
    (net (code "65") (name "/XOUT") (class "Default")
      (node (ref "R10") (pin "2") (pintype "passive"))
      (node (ref "U1") (pin "31") (pinfunction "XOUT_31") (pintype "passive"))
    )
    (net (code "66") (name "GND") (class "Default")
      (node (ref "C1") (pin "2") (pintype "passive"))
      (node (ref "C10") (pin "2") (pintype "passive"))
      (node (ref "C11") (pin "2") (pintype "passive"))
      (node (ref "C12") (pin "2") (pintype "passive"))
      (node (ref "C13") (pin "2") (pintype "passive"))
      (node (ref "C14") (pin "2") (pintype "passive"))
      (node (ref "C15") (pin "2") (pintype "passive"))
      (node (ref "C16") (pin "2") (pintype "passive"))
      (node (ref "C17") (pin "2") (pintype "passive"))
      (node (ref "C18") (pin "2") (pintype "passive"))
      (node (ref "C19") (pin "2") (pintype "passive"))
      (node (ref "C2") (pin "2") (pintype "passive"))
      (node (ref "C20") (pin "2") (pintype "passive"))
      (node (ref "C21") (pin "2") (pintype "passive"))
      (node (ref "C22") (pin "2") (pintype "passive"))
      (node (ref "C23") (pin "2") (pintype "passive"))
      (node (ref "C24") (pin "2") (pintype "passive"))
      (node (ref "C25") (pin "2") (pintype "passive"))
      (node (ref "C26") (pin "2") (pintype "passive"))
      (node (ref "C27") (pin "2") (pintype "passive"))
      (node (ref "C28") (pin "2") (pintype "passive"))
      (node (ref "C29") (pin "2") (pintype "passive"))
      (node (ref "C30") (pin "2") (pintype "passive"))
      (node (ref "C31") (pin "2") (pintype "passive"))
      (node (ref "C32") (pin "2") (pintype "passive"))
      (node (ref "C33") (pin "2") (pintype "passive"))
      (node (ref "C34") (pin "2") (pintype "passive"))
      (node (ref "C35") (pin "2") (pintype "passive"))
      (node (ref "C36") (pin "2") (pintype "passive"))
      (node (ref "C37") (pin "2") (pintype "passive"))
      (node (ref "C38") (pin "2") (pintype "passive"))
      (node (ref "C39") (pin "2") (pintype "passive"))
      (node (ref "C4") (pin "2") (pintype "passive"))
      (node (ref "C40") (pin "2") (pintype "passive"))
      (node (ref "C5") (pin "2") (pintype "passive"))
      (node (ref "C6") (pin "2") (pintype "passive"))
      (node (ref "C7") (pin "2") (pintype "passive"))
      (node (ref "C8") (pin "2") (pintype "passive"))
      (node (ref "C9") (pin "2") (pintype "passive"))
      (node (ref "D1") (pin "2") (pinfunction "A_2") (pintype "passive"))
      (node (ref "D2") (pin "1") (pinfunction "A_1") (pintype "passive"))
      (node (ref "J1") (pin "A1") (pinfunction "A1_A1") (pintype "passive"))
      (node (ref "J1") (pin "A12") (pinfunction "A12_A12") (pintype "passive"))
      (node (ref "J1") (pin "B1") (pinfunction "B1_B1") (pintype "passive"))
      (node (ref "J1") (pin "B12") (pinfunction "B12_B12") (pintype "passive"))
      (node (ref "J2") (pin "1") (pinfunction "1_1") (pintype "passive"))
      (node (ref "J2") (pin "33") (pinfunction "33_33") (pintype "passive"))
      (node (ref "J2") (pin "5") (pinfunction "5_5") (pintype "passive"))
      (node (ref "J2") (pin "60") (pinfunction "36_60") (pintype "passive"))
      (node (ref "J2") (pin "61") (pinfunction "37_61") (pintype "passive"))
      (node (ref "K1") (pin "2") (pinfunction "-_2") (pintype "passive"))
      (node (ref "R15") (pin "2") (pintype "passive"))
      (node (ref "R2") (pin "2") (pintype "passive"))
      (node (ref "R3") (pin "2") (pintype "passive"))
      (node (ref "SW1") (pin "3") (pinfunction "3_3") (pintype "passive"))
      (node (ref "SW2") (pin "4") (pinfunction "4_4") (pintype "passive"))
      (node (ref "SW3") (pin "4") (pinfunction "4_4") (pintype "passive"))
      (node (ref "U1") (pin "62") (pinfunction "VRPGND_62") (pintype "passive"))
      (node (ref "U1") (pin "81") (pinfunction "PAD(GND)_81") (pintype "passive"))
      (node (ref "U2") (pin "4") (pinfunction "GND_4") (pintype "passive"))
      (node (ref "U3") (pin "4") (pinfunction "GND_4") (pintype "passive"))
      (node (ref "U4") (pin "2") (pinfunction "2_2") (pintype "passive"))
      (node (ref "U4") (pin "3") (pinfunction "3_3") (pintype "passive"))
      (node (ref "U5") (pin "4") (pinfunction "GND_4") (pintype "passive"))
      (node (ref "U6") (pin "1") (pinfunction "A0_1") (pintype "input"))
      (node (ref "U6") (pin "2") (pinfunction "A1_2") (pintype "input"))
      (node (ref "U6") (pin "3") (pinfunction "A2_3") (pintype "input"))
      (node (ref "U6") (pin "4") (pinfunction "GND_4") (pintype "power_in"))
      (node (ref "U7") (pin "4") (pinfunction "GND_4") (pintype "power_in"))
      (node (ref "U8") (pin "5") (pinfunction "GND_5") (pintype "power_in"))
      (node (ref "U9") (pin "2") (pinfunction "GND_2") (pintype "passive"))
      (node (ref "X1") (pin "2") (pinfunction "2_2") (pintype "passive"))
      (node (ref "X1") (pin "4") (pinfunction "4_4") (pintype "passive"))
    )
    (net (code "67") (name "Net-(C26-Pad1)") (class "Default")
      (node (ref "C26") (pin "1") (pintype "passive"))
      (node (ref "R10") (pin "1") (pintype "passive"))
      (node (ref "X1") (pin "3") (pinfunction "3_3") (pintype "passive"))
    )
    (net (code "68") (name "Net-(D2-K)") (class "Default")
      (node (ref "D2") (pin "2") (pinfunction "K_2") (pintype "passive"))
      (node (ref "R7") (pin "2") (pintype "passive"))
    )
    (net (code "69") (name "Net-(D3-A)") (class "Default")
      (node (ref "D3") (pin "2") (pinfunction "A_2") (pintype "passive"))
      (node (ref "R18") (pin "1") (pintype "passive"))
    )
    (net (code "70") (name "Net-(D3-K)") (class "Default")
      (node (ref "D3") (pin "1") (pinfunction "K_1") (pintype "passive"))
      (node (ref "K1") (pin "1") (pinfunction "+_1") (pintype "passive"))
      (node (ref "R17") (pin "2") (pintype "passive"))
    )
    (net (code "71") (name "Net-(J1-PadA5)") (class "Default")
      (node (ref "J1") (pin "A5") (pinfunction "A5_A5") (pintype "passive"))
      (node (ref "R2") (pin "1") (pintype "passive"))
    )
    (net (code "72") (name "Net-(J1-PadA6)") (class "Default")
      (node (ref "J1") (pin "A6") (pinfunction "A6_A6") (pintype "passive"))
      (node (ref "J1") (pin "B6") (pinfunction "B6_B6") (pintype "passive"))
      (node (ref "R5") (pin "1") (pintype "passive"))
    )
    (net (code "73") (name "Net-(J1-PadA7)") (class "Default")
      (node (ref "J1") (pin "A7") (pinfunction "A7_A7") (pintype "passive"))
      (node (ref "J1") (pin "B7") (pinfunction "B7_B7") (pintype "passive"))
      (node (ref "R4") (pin "1") (pintype "passive"))
    )
    (net (code "74") (name "Net-(J1-PadB5)") (class "Default")
      (node (ref "J1") (pin "B5") (pinfunction "B5_B5") (pintype "passive"))
      (node (ref "R3") (pin "1") (pintype "passive"))
    )
    (net (code "75") (name "Net-(J4-Pad1)") (class "Default")
      (node (ref "J4") (pin "1") (pinfunction "1_1") (pintype "passive"))
      (node (ref "R7") (pin "1") (pintype "passive"))
    )
    (net (code "76") (name "Net-(U1-ADC_IOVDD)") (class "Default")
      (node (ref "C18") (pin "1") (pintype "passive"))
      (node (ref "C31") (pin "1") (pintype "passive"))
      (node (ref "R16") (pin "2") (pintype "passive"))
      (node (ref "U1") (pin "59") (pinfunction "ADC_IOVDD_59") (pintype "passive"))
    )
    (net (code "77") (name "Net-(U1-GPIO47)") (class "Default")
      (node (ref "J5") (pin "2") (pinfunction "2_2") (pintype "passive"))
      (node (ref "U1") (pin "58") (pinfunction "GPIO47_58") (pintype "passive"))
    )
    (net (code "78") (name "Net-(U1-USB_DN)") (class "Default")
      (node (ref "D1") (pin "4") (pinfunction "A_4") (pintype "passive"))
      (node (ref "R4") (pin "2") (pintype "passive"))
      (node (ref "U1") (pin "66") (pinfunction "USB_DN_66") (pintype "passive"))
    )
    (net (code "79") (name "Net-(U1-USB_DP)") (class "Default")
      (node (ref "D1") (pin "3") (pinfunction "A_3") (pintype "passive"))
      (node (ref "R5") (pin "2") (pintype "passive"))
      (node (ref "U1") (pin "67") (pinfunction "USB_DP_67") (pintype "passive"))
    )
    (net (code "80") (name "Net-(U1-VRLX)") (class "Default")
      (node (ref "L2") (pin "2") (pinfunction "2_2") (pintype "passive"))
      (node (ref "U1") (pin "63") (pinfunction "VRLX_63") (pintype "passive"))
    )
    (net (code "81") (name "Net-(U2-BST)") (class "Default")
      (node (ref "C3") (pin "2") (pintype "passive"))
      (node (ref "U2") (pin "6") (pinfunction "BST_6") (pintype "passive"))
    )
    (net (code "82") (name "Net-(U2-EN)") (class "Default")
      (node (ref "R1") (pin "1") (pintype "passive"))
      (node (ref "U2") (pin "2") (pinfunction "EN_2") (pintype "passive"))
    )
    (net (code "83") (name "Net-(U2-SW)") (class "Default")
      (node (ref "C3") (pin "1") (pintype "passive"))
      (node (ref "L1") (pin "1") (pinfunction "1_1") (pintype "passive"))
      (node (ref "U2") (pin "5") (pinfunction "SW_5") (pintype "passive"))
    )
    (net (code "84") (name "Net-(U7-X1)") (class "Default")
      (node (ref "C37") (pin "1") (pintype "passive"))
      (node (ref "U7") (pin "1") (pinfunction "X1_1") (pintype "input"))
      (node (ref "X2") (pin "1") (pinfunction "OSC1_1") (pintype "passive"))
    )
    (net (code "85") (name "Net-(U7-XO)") (class "Default")
      (node (ref "C36") (pin "1") (pintype "passive"))
      (node (ref "U7") (pin "2") (pinfunction "XO_2") (pintype "output"))
      (node (ref "X2") (pin "2") (pinfunction "OSC2_2") (pintype "passive"))
    )
    (net (code "86") (name "Net-(U8-~{INT}{slash}SQW)") (class "Default")
      (node (ref "J7") (pin "1") (pinfunction "1_1") (pintype "passive"))
      (node (ref "U8") (pin "3") (pinfunction "~{INT}/SQW_3") (pintype "output"))
    )
    (net (code "87") (name "Net-(U8-~{RST})") (class "Default")
      (node (ref "J6") (pin "2") (pinfunction "2_2") (pintype "passive"))
      (node (ref "U8") (pin "4") (pinfunction "~{RST}_4") (pintype "bidirectional"))
    )
    (net (code "88") (name "P3V3") (class "Default")
      (node (ref "C10") (pin "1") (pintype "passive"))
      (node (ref "C11") (pin "1") (pintype "passive"))
      (node (ref "C12") (pin "1") (pintype "passive"))
      (node (ref "C13") (pin "1") (pintype "passive"))
      (node (ref "C14") (pin "1") (pintype "passive"))
      (node (ref "C15") (pin "1") (pintype "passive"))
      (node (ref "C16") (pin "1") (pintype "passive"))
      (node (ref "C17") (pin "1") (pintype "passive"))
      (node (ref "C19") (pin "1") (pintype "passive"))
      (node (ref "C20") (pin "1") (pintype "passive"))
      (node (ref "C21") (pin "1") (pintype "passive"))
      (node (ref "C22") (pin "1") (pintype "passive"))
      (node (ref "C24") (pin "1") (pintype "passive"))
      (node (ref "C34") (pin "1") (pintype "passive"))
      (node (ref "C35") (pin "1") (pintype "passive"))
      (node (ref "C39") (pin "1") (pintype "passive"))
      (node (ref "C6") (pin "1") (pintype "passive"))
      (node (ref "C7") (pin "1") (pintype "passive"))
      (node (ref "C8") (pin "1") (pintype "passive"))
      (node (ref "C9") (pin "1") (pintype "passive"))
      (node (ref "J2") (pin "32") (pinfunction "32_32") (pintype "passive"))
      (node (ref "J2") (pin "63") (pinfunction "39_63") (pintype "passive"))
      (node (ref "J3") (pin "1") (pinfunction "1_1") (pintype "passive"))
      (node (ref "R11") (pin "2") (pintype "passive"))
      (node (ref "R12") (pin "1") (pintype "passive"))
      (node (ref "R13") (pin "1") (pintype "passive"))
      (node (ref "R14") (pin "2") (pintype "passive"))
      (node (ref "R16") (pin "1") (pintype "passive"))
      (node (ref "R18") (pin "2") (pintype "passive"))
      (node (ref "R8") (pin "2") (pintype "passive"))
      (node (ref "R9") (pin "2") (pintype "passive"))
      (node (ref "U1") (pin "15") (pinfunction "IOVDD_15") (pintype "passive"))
      (node (ref "U1") (pin "24") (pinfunction "IOVDD_24") (pintype "passive"))
      (node (ref "U1") (pin "29") (pinfunction "IOVDD_29") (pintype "passive"))
      (node (ref "U1") (pin "41") (pinfunction "IOVDD_41") (pintype "passive"))
      (node (ref "U1") (pin "5") (pinfunction "IOVDD_5") (pintype "passive"))
      (node (ref "U1") (pin "50") (pinfunction "IOVDD_50") (pintype "passive"))
      (node (ref "U1") (pin "60") (pinfunction "IOVDD_60") (pintype "passive"))
      (node (ref "U1") (pin "64") (pinfunction "VREGIN_64") (pintype "passive"))
      (node (ref "U1") (pin "68") (pinfunction "USBVDD_68") (pintype "passive"))
      (node (ref "U1") (pin "69") (pinfunction "QSPIVDD_69") (pintype "passive"))
      (node (ref "U1") (pin "76") (pinfunction "IOVDD_76") (pintype "passive"))
      (node (ref "U3") (pin "8") (pinfunction "VCC_8") (pintype "passive"))
      (node (ref "U5") (pin "8") (pinfunction "VCC_8") (pintype "passive"))
      (node (ref "U6") (pin "7") (pinfunction "WP_7") (pintype "passive"))
      (node (ref "U6") (pin "8") (pinfunction "VCC_8") (pintype "passive"))
      (node (ref "U7") (pin "8") (pinfunction "VCC_8") (pintype "passive"))
      (node (ref "U8") (pin "2") (pinfunction "VCC_2") (pintype "passive"))
    )
    (net (code "89") (name "P3V3OUT") (class "Default")
      (node (ref "C4") (pin "1") (pintype "passive"))
      (node (ref "C5") (pin "1") (pintype "passive"))
      (node (ref "J2") (pin "2") (pinfunction "2_2") (pintype "passive"))
      (node (ref "J3") (pin "2") (pinfunction "2_2") (pintype "passive"))
      (node (ref "L1") (pin "2") (pinfunction "2_2") (pintype "passive"))
      (node (ref "U2") (pin "1") (pinfunction "FB_1") (pintype "passive"))
    )
    (net (code "90") (name "SHLD") (class "Default")
      (node (ref "C33") (pin "1") (pintype "passive"))
      (node (ref "J1") (pin "1") (pinfunction "1_1") (pintype "passive"))
      (node (ref "J1") (pin "2") (pinfunction "2_2") (pintype "passive"))
      (node (ref "J1") (pin "3") (pinfunction "3_3") (pintype "passive"))
      (node (ref "J1") (pin "4") (pinfunction "4_4") (pintype "passive"))
      (node (ref "R15") (pin "1") (pintype "passive"))
    )
    (net (code "91") (name "VBUS") (class "Default")
      (node (ref "C32") (pin "1") (pintype "passive"))
      (node (ref "C40") (pin "1") (pintype "passive"))
      (node (ref "D1") (pin "5") (pinfunction "A_5") (pintype "passive"))
      (node (ref "J1") (pin "A4") (pinfunction "A4_A4") (pintype "passive"))
      (node (ref "J1") (pin "A9") (pinfunction "A9_A9") (pintype "passive"))
      (node (ref "J1") (pin "B4") (pinfunction "B4_B4") (pintype "passive"))
      (node (ref "J1") (pin "B9") (pinfunction "B9_B9") (pintype "passive"))
      (node (ref "J8") (pin "2") (pinfunction "2_2") (pintype "passive"))
      (node (ref "U9") (pin "1") (pinfunction "VIN_1") (pintype "passive"))
      (node (ref "U9") (pin "3") (pinfunction "CE_3") (pintype "passive"))
    )
    (net (code "92") (name "VREF") (class "Default")
      (node (ref "C23") (pin "1") (pintype "passive"))
      (node (ref "J2") (pin "4") (pinfunction "4_4") (pintype "passive"))
      (node (ref "R11") (pin "1") (pintype "passive"))
      (node (ref "U1") (pin "61") (pinfunction "VRAVDD_61") (pintype "passive"))
      (node (ref "U4") (pin "1") (pinfunction "1_1") (pintype "passive"))
    )
    (net (code "93") (name "VSYS") (class "Default")
      (node (ref "C1") (pin "1") (pintype "passive"))
      (node (ref "C2") (pin "1") (pintype "passive"))
      (node (ref "J2") (pin "64") (pinfunction "40_64") (pintype "passive"))
      (node (ref "J8") (pin "1") (pinfunction "1_1") (pintype "passive"))
      (node (ref "R1") (pin "2") (pintype "passive"))
      (node (ref "U2") (pin "3") (pinfunction "VIN_3") (pintype "passive"))
      (node (ref "U9") (pin "5") (pinfunction "VOUT_5") (pintype "passive"))
    )
    (net (code "94") (name "unconnected-(J1-PadA8)") (class "Default")
      (node (ref "J1") (pin "A8") (pinfunction "A8_A8") (pintype "passive"))
    )
    (net (code "95") (name "unconnected-(J1-PadB8)") (class "Default")
      (node (ref "J1") (pin "B8") (pinfunction "B8_B8") (pintype "passive"))
    )
    (net (code "96") (name "unconnected-(SW1-Pad1)") (class "Default")
      (node (ref "SW1") (pin "1") (pinfunction "1_1") (pintype "passive"))
    )
    (net (code "97") (name "unconnected-(SW1-Pad4)") (class "Default")
      (node (ref "SW1") (pin "4") (pinfunction "4_4") (pintype "passive"))
    )
    (net (code "98") (name "unconnected-(SW2-Pad1)") (class "Default")
      (node (ref "SW2") (pin "1") (pinfunction "1_1") (pintype "passive"))
    )
    (net (code "99") (name "unconnected-(SW2-Pad3)") (class "Default")
      (node (ref "SW2") (pin "3") (pinfunction "3_3") (pintype "passive"))
    )
    (net (code "100") (name "unconnected-(SW3-Pad1)") (class "Default")
      (node (ref "SW3") (pin "1") (pinfunction "1_1") (pintype "passive"))
    )
    (net (code "101") (name "unconnected-(SW3-Pad3)") (class "Default")
      (node (ref "SW3") (pin "3") (pinfunction "3_3") (pintype "passive"))
    )
    (net (code "102") (name "unconnected-(U7-FT-Pad1)") (class "Default")
      (node (ref "U7") (pin "1") (pinfunction "FT_1") (pintype "output"))
    )
    (net (code "103") (name "unconnected-(U8-32KHz-Pad1)") (class "Default")
      (node (ref "U8") (pin "1") (pinfunction "32KHz_1") (pintype "output"))
    )
  )
)
